# aspirin.net
KiCad netlist of a schematic drawn in EAGLE
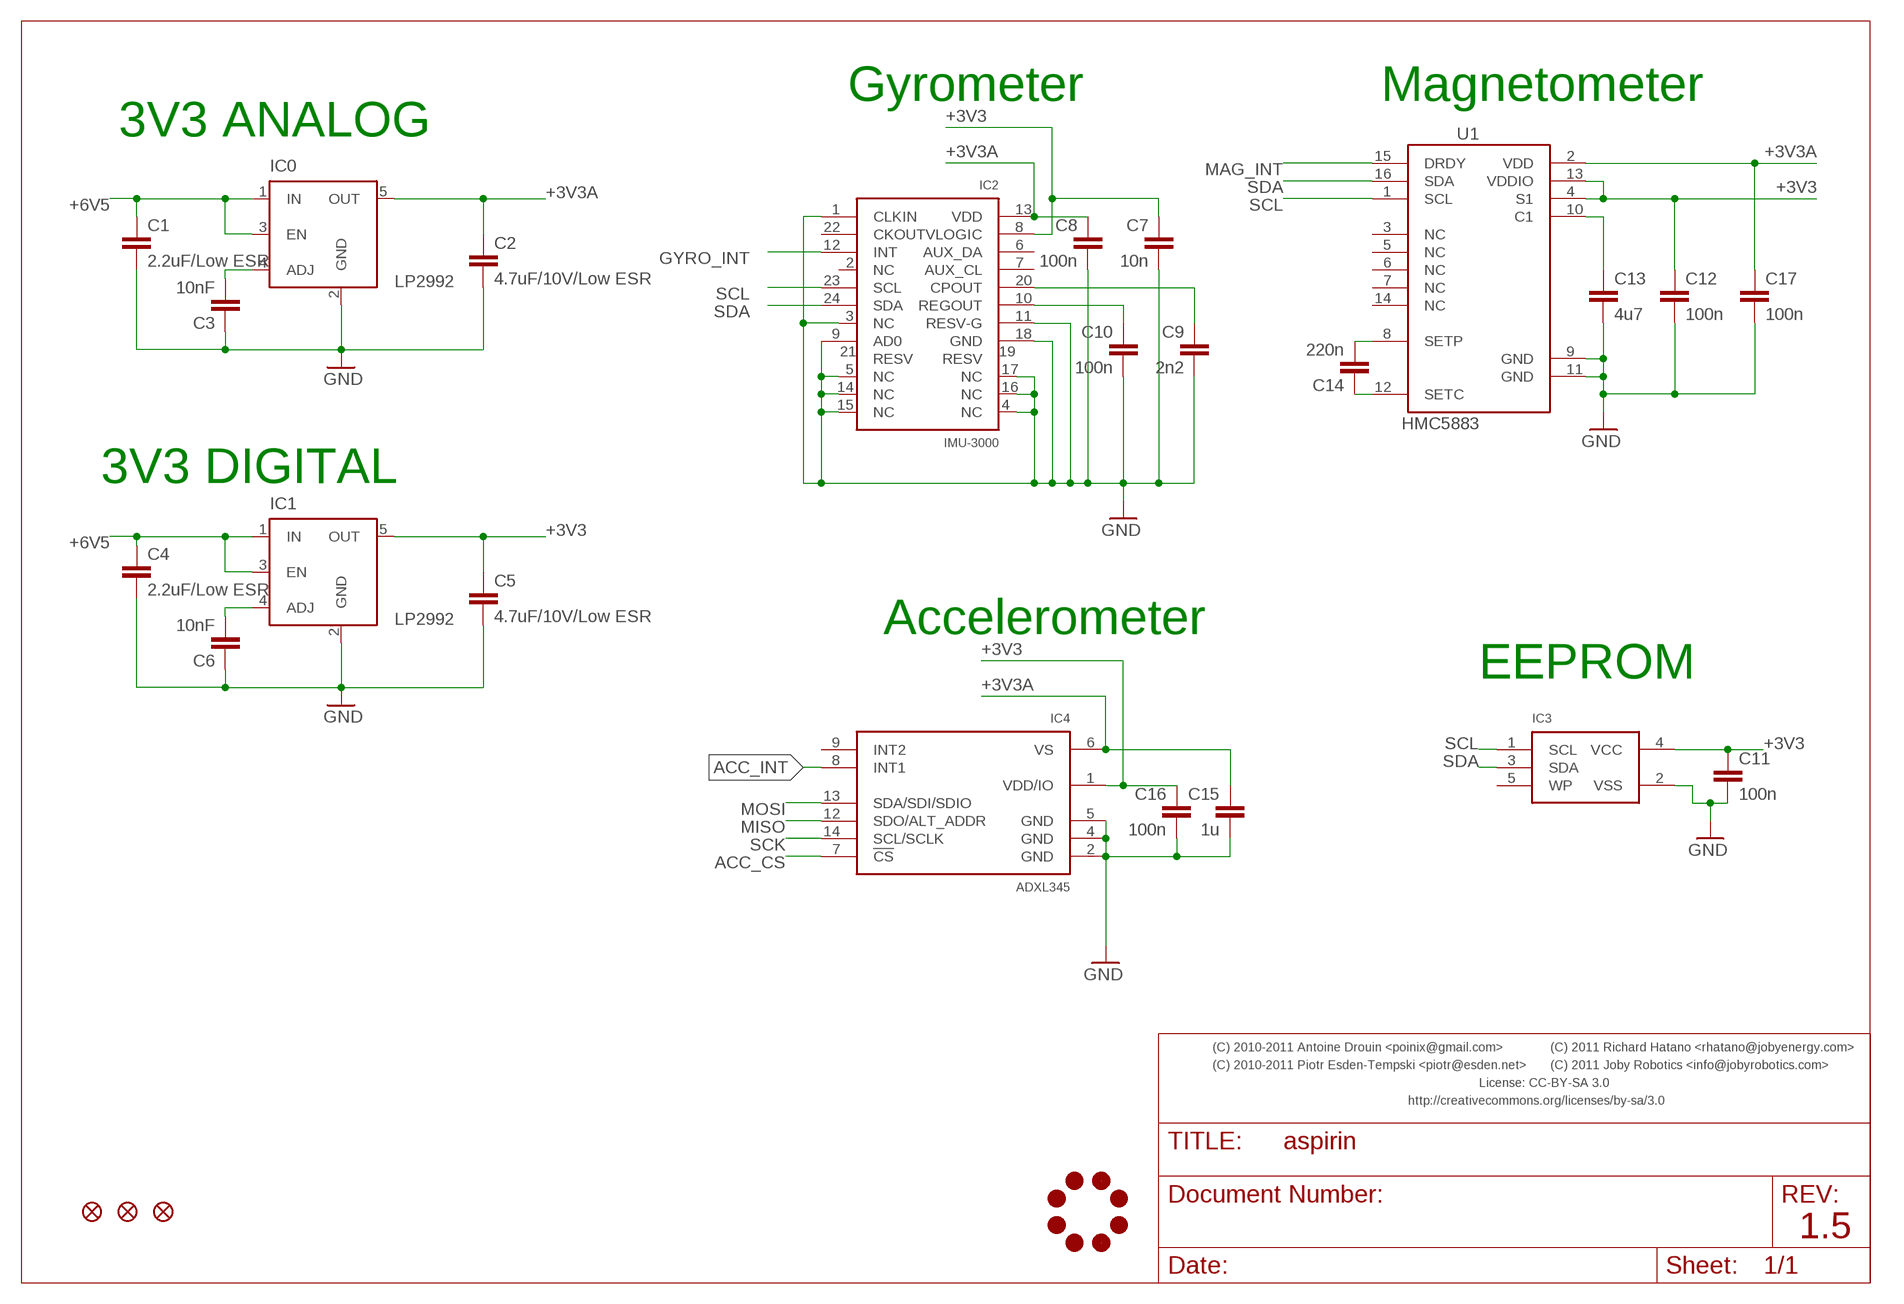
[diagram p0: schematic, sheet 1]

(export (version "E")
  (design (tool "Eeschema 10.0.6"))
  (components
    (comp (ref "C1")
      (value "2.2uF/Low ESR")
      (footprint "eagle-import:0603-CAP")
      (libsource (lib "eagle-import") (part "CAPACITOR-0603"))
    )
    (comp (ref "C2")
      (value "4.7uF/10V/Low ESR")
      (footprint "eagle-import:0402-CAP")
      (libsource (lib "eagle-import") (part "CAPACITOR-0402"))
    )
    (comp (ref "C3")
      (value "10nF")
      (footprint "eagle-import:0402-CAP")
      (libsource (lib "eagle-import") (part "CAPACITOR-0402"))
    )
    (comp (ref "C4")
      (value "2.2uF/Low ESR")
      (footprint "eagle-import:0603-CAP")
      (libsource (lib "eagle-import") (part "CAPACITOR-0603"))
    )
    (comp (ref "C5")
      (value "4.7uF/10V/Low ESR")
      (footprint "eagle-import:0402-CAP")
      (libsource (lib "eagle-import") (part "CAPACITOR-0402"))
    )
    (comp (ref "C6")
      (value "10nF")
      (footprint "eagle-import:0402-CAP")
      (libsource (lib "eagle-import") (part "CAPACITOR-0402"))
    )
    (comp (ref "C7")
      (value "10n")
      (footprint "eagle-import:0402-CAP")
      (libsource (lib "eagle-import") (part "CAPACITOR-0402"))
    )
    (comp (ref "C8")
      (value "100n")
      (footprint "eagle-import:0402-CAP")
      (libsource (lib "eagle-import") (part "CAPACITOR-0402"))
    )
    (comp (ref "C9")
      (value "2n2")
      (footprint "eagle-import:0402-CAP")
      (libsource (lib "eagle-import") (part "CAPACITOR-0402"))
    )
    (comp (ref "C10")
      (value "100n")
      (footprint "eagle-import:0402-CAP")
      (libsource (lib "eagle-import") (part "CAPACITOR-0402"))
    )
    (comp (ref "C11")
      (value "100n")
      (footprint "eagle-import:0402-CAP")
      (libsource (lib "eagle-import") (part "CAPACITOR-0402"))
    )
    (comp (ref "C12")
      (value "100n")
      (footprint "eagle-import:0402-CAP")
      (libsource (lib "eagle-import") (part "CAPACITOR-0402"))
    )
    (comp (ref "C13")
      (value "4u7")
      (footprint "eagle-import:0402-CAP")
      (libsource (lib "eagle-import") (part "CAPACITOR-0402"))
    )
    (comp (ref "C14")
      (value "220n")
      (footprint "eagle-import:0402-CAP")
      (libsource (lib "eagle-import") (part "CAPACITOR-0402"))
    )
    (comp (ref "C15")
      (value "1u")
      (footprint "eagle-import:0402-CAP")
      (libsource (lib "eagle-import") (part "CAPACITOR-0402"))
    )
    (comp (ref "C16")
      (value "100n")
      (footprint "eagle-import:0402-CAP")
      (libsource (lib "eagle-import") (part "CAPACITOR-0402"))
    )
    (comp (ref "C17")
      (value "100n")
      (footprint "eagle-import:0402-CAP")
      (libsource (lib "eagle-import") (part "CAPACITOR-0402"))
    )
    (comp (ref "IC0")
      (value "LP2992")
      (footprint "eagle-import:SOT23-5")
      (libsource (lib "eagle-import") (part "MIC5219BM5"))
    )
    (comp (ref "IC1")
      (value "LP2992")
      (footprint "eagle-import:SOT23-5")
      (libsource (lib "eagle-import") (part "MIC5219BM5"))
    )
    (comp (ref "IC2")
      (value "IMU-3000")
      (footprint "eagle-import:QFN24-IMU3000")
      (libsource (lib "eagle-import") (part "IMU-3000"))
    )
    (comp (ref "IC3")
      (value "I2C_EEPROM-SOT23-5")
      (footprint "eagle-import:SOT23-5")
      (libsource (lib "eagle-import") (part "I2C_EEPROM-SOT23-5"))
    )
    (comp (ref "IC4")
      (value "ADXL345")
      (footprint "eagle-import:LGA-14")
      (libsource (lib "eagle-import") (part "ADXL345"))
    )
    (comp (ref "JL2")
      (value "JOBY_LOGO-6MIL")
      (footprint "eagle-import:JOBY_LOGO_6MIL")
      (libsource (lib "eagle-import") (part "JOBY_LOGO-6MIL"))
    )
    (comp (ref "JP1")
      (value "FIDUCIAL1X2")
      (footprint "eagle-import:FIDUCIAL-1X2")
      (libsource (lib "eagle-import") (part "FIDUCIAL1X2"))
    )
    (comp (ref "JP2")
      (value "FIDUCIAL1X2")
      (footprint "eagle-import:FIDUCIAL-1X2")
      (libsource (lib "eagle-import") (part "FIDUCIAL1X2"))
    )
    (comp (ref "JP3")
      (value "FIDUCIAL1X2")
      (footprint "eagle-import:FIDUCIAL-1X2")
      (libsource (lib "eagle-import") (part "FIDUCIAL1X2"))
    )
    (comp (ref "U1")
      (value "HMC5883")
      (footprint "eagle-import:PLCC16-HMC5883")
      (libsource (lib "eagle-import") (part "HMC5883"))
    )
  )
  (nets
    (net (code "1") (name "/+3V3") (class "Default")
      (node (ref "C11") (pin "P$1") (pinfunction "1_P$1") (pintype "passive"))
      (node (ref "C12") (pin "P$1") (pinfunction "1_P$1") (pintype "passive"))
      (node (ref "C16") (pin "P$1") (pinfunction "1_P$1") (pintype "passive"))
      (node (ref "C5") (pin "P$1") (pinfunction "1_P$1") (pintype "passive"))
      (node (ref "C7") (pin "P$1") (pinfunction "1_P$1") (pintype "passive"))
      (node (ref "IC1") (pin "5") (pinfunction "OUT_5") (pintype "output"))
      (node (ref "IC2") (pin "8") (pinfunction "VLOGIC_8") (pintype "bidirectional"))
      (node (ref "IC3") (pin "4") (pinfunction "VCC_4") (pintype "bidirectional"))
      (node (ref "IC4") (pin "1") (pinfunction "VDD/IO_1") (pintype "bidirectional"))
      (node (ref "U1") (pin "13") (pinfunction "VDDIO_13") (pintype "power_in"))
      (node (ref "U1") (pin "4") (pinfunction "S1_4") (pintype "power_in"))
    )
    (net (code "2") (name "/+3V3A") (class "Default")
      (node (ref "C15") (pin "P$1") (pinfunction "1_P$1") (pintype "passive"))
      (node (ref "C17") (pin "P$1") (pinfunction "1_P$1") (pintype "passive"))
      (node (ref "C2") (pin "P$1") (pinfunction "1_P$1") (pintype "passive"))
      (node (ref "C8") (pin "P$1") (pinfunction "1_P$1") (pintype "passive"))
      (node (ref "IC0") (pin "5") (pinfunction "OUT_5") (pintype "output"))
      (node (ref "IC2") (pin "13") (pinfunction "VDD_13") (pintype "bidirectional"))
      (node (ref "IC4") (pin "6") (pinfunction "VS_6") (pintype "bidirectional"))
      (node (ref "U1") (pin "2") (pinfunction "VDD_2") (pintype "power_in"))
    )
    (net (code "3") (name "/+6V5") (class "Default")
      (node (ref "C1") (pin "P$1") (pinfunction "1_P$1") (pintype "passive"))
      (node (ref "C4") (pin "P$1") (pinfunction "1_P$1") (pintype "passive"))
      (node (ref "IC0") (pin "1") (pinfunction "IN_1") (pintype "input"))
      (node (ref "IC0") (pin "3") (pinfunction "EN_3") (pintype "input"))
      (node (ref "IC1") (pin "1") (pinfunction "IN_1") (pintype "input"))
      (node (ref "IC1") (pin "3") (pinfunction "EN_3") (pintype "input"))
    )
    (net (code "4") (name "/ACC_CS") (class "Default")
      (node (ref "IC4") (pin "7") (pinfunction "~{CS}_7") (pintype "bidirectional"))
    )
    (net (code "5") (name "/GYRO_INT") (class "Default")
      (node (ref "IC2") (pin "12") (pinfunction "INT_12") (pintype "bidirectional"))
    )
    (net (code "6") (name "/MAG_INT") (class "Default")
      (node (ref "U1") (pin "15") (pinfunction "DRDY_15") (pintype "bidirectional"))
    )
    (net (code "7") (name "/MISO") (class "Default")
      (node (ref "IC4") (pin "12") (pinfunction "SDO/ALT_ADDR_12") (pintype "bidirectional"))
    )
    (net (code "8") (name "/MOSI") (class "Default")
      (node (ref "IC4") (pin "13") (pinfunction "SDA/SDI/SDIO_13") (pintype "bidirectional"))
    )
    (net (code "9") (name "/SCK") (class "Default")
      (node (ref "IC4") (pin "14") (pinfunction "SCL/SCLK_14") (pintype "bidirectional"))
    )
    (net (code "10") (name "/SCL") (class "Default")
      (node (ref "IC2") (pin "23") (pinfunction "SCL_23") (pintype "bidirectional"))
      (node (ref "IC3") (pin "1") (pinfunction "SCL_1") (pintype "bidirectional"))
      (node (ref "U1") (pin "1") (pinfunction "SCL_1") (pintype "bidirectional"))
    )
    (net (code "11") (name "/SDA") (class "Default")
      (node (ref "IC2") (pin "24") (pinfunction "SDA_24") (pintype "bidirectional"))
      (node (ref "IC3") (pin "3") (pinfunction "SDA_3") (pintype "bidirectional"))
      (node (ref "U1") (pin "16") (pinfunction "SDA_16") (pintype "bidirectional"))
    )
    (net (code "12") (name "ACC_INT") (class "Default")
      (node (ref "IC4") (pin "8") (pinfunction "INT1_8") (pintype "bidirectional"))
    )
    (net (code "13") (name "GND") (class "Default")
      (node (ref "C1") (pin "P$2") (pinfunction "2_P$2") (pintype "passive"))
      (node (ref "C10") (pin "P$2") (pinfunction "2_P$2") (pintype "passive"))
      (node (ref "C11") (pin "P$2") (pinfunction "2_P$2") (pintype "passive"))
      (node (ref "C12") (pin "P$2") (pinfunction "2_P$2") (pintype "passive"))
      (node (ref "C13") (pin "P$2") (pinfunction "2_P$2") (pintype "passive"))
      (node (ref "C15") (pin "P$2") (pinfunction "2_P$2") (pintype "passive"))
      (node (ref "C16") (pin "P$2") (pinfunction "2_P$2") (pintype "passive"))
      (node (ref "C17") (pin "P$2") (pinfunction "2_P$2") (pintype "passive"))
      (node (ref "C2") (pin "P$2") (pinfunction "2_P$2") (pintype "passive"))
      (node (ref "C3") (pin "P$1") (pinfunction "1_P$1") (pintype "passive"))
      (node (ref "C4") (pin "P$2") (pinfunction "2_P$2") (pintype "passive"))
      (node (ref "C5") (pin "P$2") (pinfunction "2_P$2") (pintype "passive"))
      (node (ref "C6") (pin "P$1") (pinfunction "1_P$1") (pintype "passive"))
      (node (ref "C7") (pin "P$2") (pinfunction "2_P$2") (pintype "passive"))
      (node (ref "C8") (pin "P$2") (pinfunction "2_P$2") (pintype "passive"))
      (node (ref "C9") (pin "P$2") (pinfunction "2_P$2") (pintype "passive"))
      (node (ref "IC0") (pin "2") (pinfunction "GND_2") (pintype "power_in"))
      (node (ref "IC1") (pin "2") (pinfunction "GND_2") (pintype "power_in"))
      (node (ref "IC2") (pin "1") (pinfunction "CLKIN_1") (pintype "bidirectional"))
      (node (ref "IC2") (pin "11") (pinfunction "RESV-G_11") (pintype "bidirectional"))
      (node (ref "IC2") (pin "14") (pinfunction "NC_14") (pintype "bidirectional"))
      (node (ref "IC2") (pin "15") (pinfunction "NC_15") (pintype "bidirectional"))
      (node (ref "IC2") (pin "16") (pinfunction "NC_16") (pintype "bidirectional"))
      (node (ref "IC2") (pin "17") (pinfunction "NC_17") (pintype "bidirectional"))
      (node (ref "IC2") (pin "18") (pinfunction "GND_18") (pintype "bidirectional"))
      (node (ref "IC2") (pin "3") (pinfunction "NC_3") (pintype "bidirectional"))
      (node (ref "IC2") (pin "4") (pinfunction "NC_4") (pintype "bidirectional"))
      (node (ref "IC2") (pin "5") (pinfunction "NC_5") (pintype "bidirectional"))
      (node (ref "IC2") (pin "9") (pinfunction "AD0_9") (pintype "bidirectional"))
      (node (ref "IC3") (pin "2") (pinfunction "VSS_2") (pintype "bidirectional"))
      (node (ref "IC4") (pin "2") (pinfunction "GND_2") (pintype "bidirectional"))
      (node (ref "IC4") (pin "4") (pinfunction "GND_4") (pintype "bidirectional"))
      (node (ref "IC4") (pin "5") (pinfunction "GND_5") (pintype "bidirectional"))
      (node (ref "U1") (pin "11") (pinfunction "GND_11") (pintype "power_in"))
      (node (ref "U1") (pin "9") (pinfunction "GND_9") (pintype "power_in"))
    )
    (net (code "14") (name "Net-(C3-2)") (class "Default")
      (node (ref "C3") (pin "P$2") (pinfunction "2_P$2") (pintype "passive"))
      (node (ref "IC0") (pin "4") (pinfunction "ADJ_4") (pintype "passive"))
    )
    (net (code "15") (name "Net-(C6-2)") (class "Default")
      (node (ref "C6") (pin "P$2") (pinfunction "2_P$2") (pintype "passive"))
      (node (ref "IC1") (pin "4") (pinfunction "ADJ_4") (pintype "passive"))
    )
    (net (code "16") (name "Net-(C9-1)") (class "Default")
      (node (ref "C9") (pin "P$1") (pinfunction "1_P$1") (pintype "passive"))
      (node (ref "IC2") (pin "20") (pinfunction "CPOUT_20") (pintype "bidirectional"))
    )
    (net (code "17") (name "Net-(C10-1)") (class "Default")
      (node (ref "C10") (pin "P$1") (pinfunction "1_P$1") (pintype "passive"))
      (node (ref "IC2") (pin "10") (pinfunction "REGOUT_10") (pintype "bidirectional"))
    )
    (net (code "18") (name "Net-(C13-1)") (class "Default")
      (node (ref "C13") (pin "P$1") (pinfunction "1_P$1") (pintype "passive"))
      (node (ref "U1") (pin "10") (pinfunction "C1_10") (pintype "bidirectional"))
    )
    (net (code "19") (name "Net-(C14-1)") (class "Default")
      (node (ref "C14") (pin "P$1") (pinfunction "1_P$1") (pintype "passive"))
      (node (ref "U1") (pin "12") (pinfunction "SETC_12") (pintype "bidirectional"))
    )
    (net (code "20") (name "Net-(C14-2)") (class "Default")
      (node (ref "C14") (pin "P$2") (pinfunction "2_P$2") (pintype "passive"))
      (node (ref "U1") (pin "8") (pinfunction "SETP_8") (pintype "bidirectional"))
    )
    (net (code "21") (name "unconnected-(IC2-AUX_CL-Pad7)") (class "Default")
      (node (ref "IC2") (pin "7") (pinfunction "AUX_CL_7") (pintype "bidirectional"))
    )
    (net (code "22") (name "unconnected-(IC2-AUX_DA-Pad6)") (class "Default")
      (node (ref "IC2") (pin "6") (pinfunction "AUX_DA_6") (pintype "bidirectional"))
    )
    (net (code "23") (name "unconnected-(IC2-CKOUT-Pad22)") (class "Default")
      (node (ref "IC2") (pin "22") (pinfunction "CKOUT_22") (pintype "bidirectional"))
    )
    (net (code "24") (name "unconnected-(IC2-NC-Pad2)") (class "Default")
      (node (ref "IC2") (pin "2") (pinfunction "NC_2") (pintype "bidirectional"))
    )
    (net (code "25") (name "unconnected-(IC2-RESV-Pad19)") (class "Default")
      (node (ref "IC2") (pin "19") (pinfunction "RESV_19") (pintype "bidirectional"))
    )
    (net (code "26") (name "unconnected-(IC2-RESV-Pad21)") (class "Default")
      (node (ref "IC2") (pin "21") (pinfunction "RESV_21") (pintype "bidirectional"))
    )
    (net (code "27") (name "unconnected-(IC3-WP-Pad5)") (class "Default")
      (node (ref "IC3") (pin "5") (pinfunction "WP_5") (pintype "bidirectional"))
    )
    (net (code "28") (name "unconnected-(IC4-INT2-Pad9)") (class "Default")
      (node (ref "IC4") (pin "9") (pinfunction "INT2_9") (pintype "bidirectional"))
    )
    (net (code "29") (name "unconnected-(U1-NC-Pad3)") (class "Default")
      (node (ref "U1") (pin "3") (pinfunction "NC_3") (pintype "no_connect"))
    )
    (net (code "30") (name "unconnected-(U1-NC-Pad5)") (class "Default")
      (node (ref "U1") (pin "5") (pinfunction "NC_5") (pintype "no_connect"))
    )
    (net (code "31") (name "unconnected-(U1-NC-Pad6)") (class "Default")
      (node (ref "U1") (pin "6") (pinfunction "NC_6") (pintype "no_connect"))
    )
    (net (code "32") (name "unconnected-(U1-NC-Pad7)") (class "Default")
      (node (ref "U1") (pin "7") (pinfunction "NC_7") (pintype "no_connect"))
    )
    (net (code "33") (name "unconnected-(U1-NC-Pad14)") (class "Default")
      (node (ref "U1") (pin "14") (pinfunction "NC_14") (pintype "no_connect"))
    )
  )
)
